# RTL8201CL.net
KiCad netlist of a schematic drawn in Altium Designer
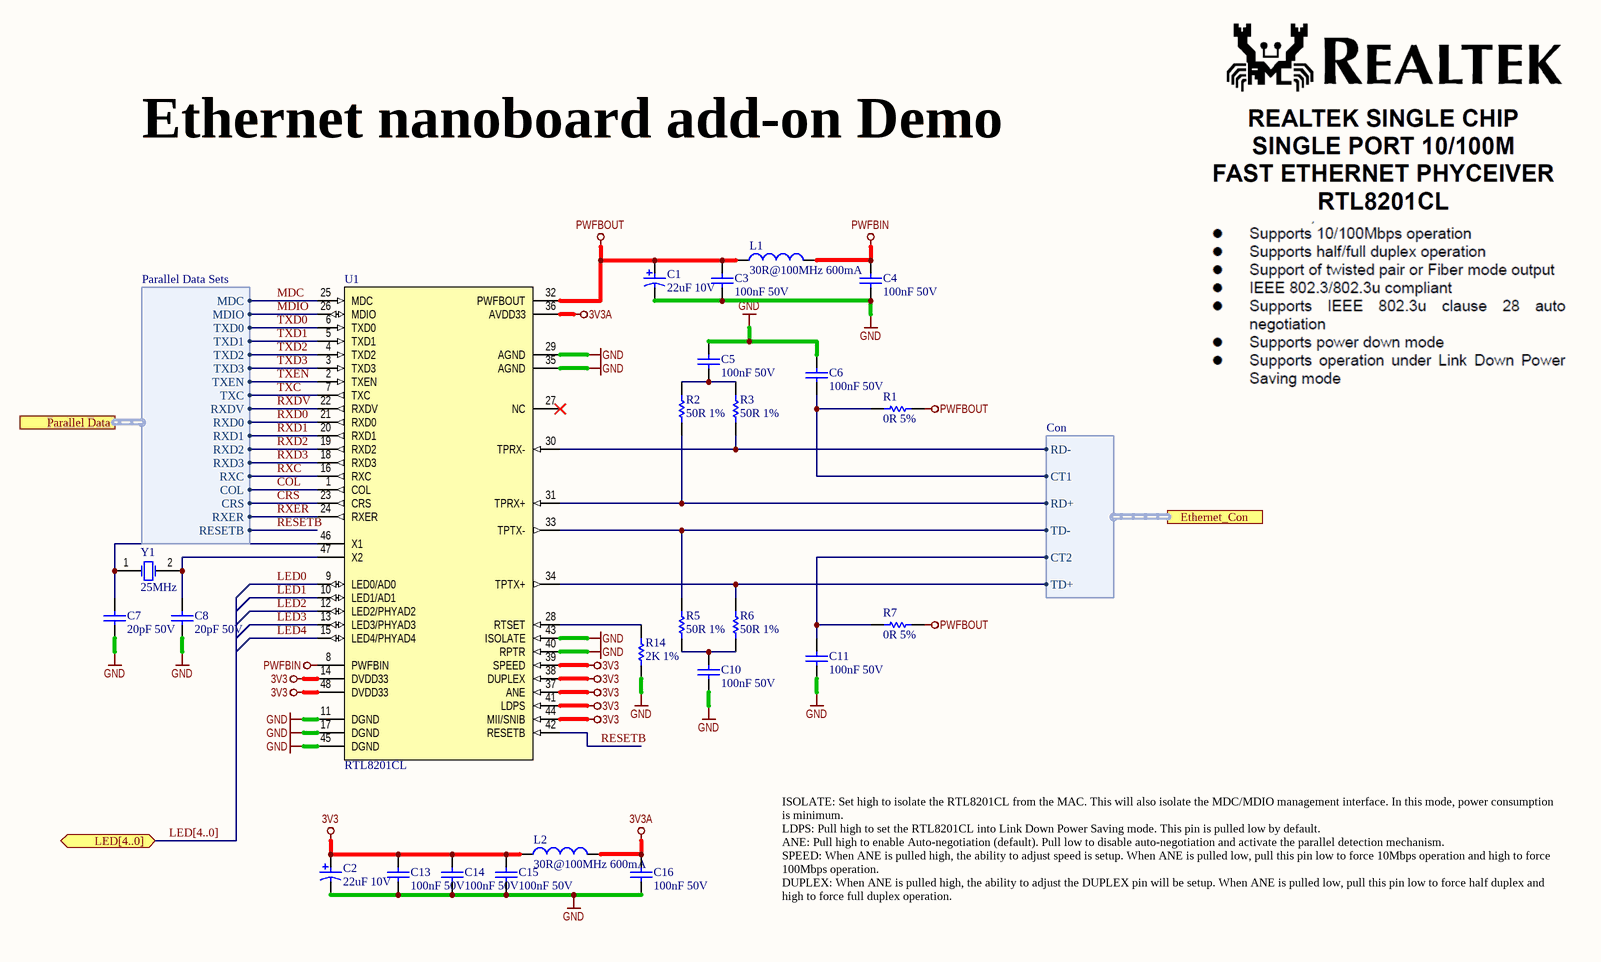
[diagram p0: RTL8201CL.SchDoc]

(export (version "E")
  (design (tool "Eeschema 10.0.6"))
  (components
    (comp (ref "C1")
      (value "22uF 10V")
      (footprint "CAPC3528")
      (description "Polar Capacitor")
      (libsource (lib "PHY") (part "CAP-P"))
    )
    (comp (ref "C2")
      (value "22uF 10V")
      (footprint "CAPC3528")
      (description "Polar Capacitor")
      (libsource (lib "PHY") (part "CAP-P"))
    )
    (comp (ref "C3")
      (value "100nF 50V")
      (footprint "CAPC2012")
      (description "Capacitor")
      (libsource (lib "PHY") (part "CAP-NP"))
    )
    (comp (ref "C4")
      (value "100nF 50V")
      (footprint "CAPC2012")
      (description "Capacitor")
      (libsource (lib "PHY") (part "CAP-NP"))
    )
    (comp (ref "C5")
      (value "100nF 50V")
      (footprint "CAPC2012")
      (description "Capacitor")
      (libsource (lib "PHY") (part "CAP-NP"))
    )
    (comp (ref "C6")
      (value "100nF 50V")
      (footprint "CAPC2012")
      (description "Capacitor")
      (libsource (lib "PHY") (part "CAP-NP"))
    )
    (comp (ref "C7")
      (value "20pF 50V")
      (footprint "CAPC2012")
      (description "Capacitor")
      (libsource (lib "PHY") (part "CAP-NP"))
    )
    (comp (ref "C8")
      (value "20pF 50V")
      (footprint "CAPC2012")
      (description "Capacitor")
      (libsource (lib "PHY") (part "CAP-NP"))
    )
    (comp (ref "C10")
      (value "100nF 50V")
      (footprint "CAPC2012")
      (description "Capacitor")
      (libsource (lib "PHY") (part "CAP-NP"))
    )
    (comp (ref "C11")
      (value "100nF 50V")
      (footprint "CAPC2012")
      (description "Capacitor")
      (libsource (lib "PHY") (part "CAP-NP"))
    )
    (comp (ref "C13")
      (value "100nF 50V")
      (footprint "CAPC2012")
      (description "Capacitor")
      (libsource (lib "PHY") (part "CAP-NP"))
    )
    (comp (ref "C14")
      (value "100nF 50V")
      (footprint "CAPC2012")
      (description "Capacitor")
      (libsource (lib "PHY") (part "CAP-NP"))
    )
    (comp (ref "C15")
      (value "100nF 50V")
      (footprint "CAPC2012")
      (description "Capacitor")
      (libsource (lib "PHY") (part "CAP-NP"))
    )
    (comp (ref "C16")
      (value "100nF 50V")
      (footprint "CAPC2012")
      (description "Capacitor")
      (libsource (lib "PHY") (part "CAP-NP"))
    )
    (comp (ref "L1")
      (value "30R@100MHz 600mA")
      (footprint "INDC2012")
      (description "Ferrite Bead")
      (libsource (lib "PHY") (part "IND-FER"))
    )
    (comp (ref "L2")
      (value "30R@100MHz 600mA")
      (footprint "INDC2012")
      (description "Ferrite Bead")
      (libsource (lib "PHY") (part "IND-FER"))
    )
    (comp (ref "R1")
      (value "0R 5%")
      (footprint "RESC2012")
      (description "Resistor")
      (libsource (lib "PHY") (part "RES"))
    )
    (comp (ref "R2")
      (value "50R 1%")
      (footprint "RESC2012")
      (description "Resistor")
      (libsource (lib "PHY") (part "RES"))
    )
    (comp (ref "R3")
      (value "50R 1%")
      (footprint "RESC2012")
      (description "Resistor")
      (libsource (lib "PHY") (part "RES"))
    )
    (comp (ref "R5")
      (value "50R 1%")
      (footprint "RESC2012")
      (description "Resistor")
      (libsource (lib "PHY") (part "RES"))
    )
    (comp (ref "R6")
      (value "50R 1%")
      (footprint "RESC2012")
      (description "Resistor")
      (libsource (lib "PHY") (part "RES"))
    )
    (comp (ref "R7")
      (value "0R 5%")
      (footprint "RESC2012")
      (description "Resistor")
      (libsource (lib "PHY") (part "RES"))
    )
    (comp (ref "R14")
      (value "2K 1%")
      (footprint "RESC2012")
      (description "Resistor")
      (libsource (lib "PHY") (part "RES"))
    )
    (comp (ref "U1")
      (value "RTL8201CL")
      (footprint "TSQFP50P900X900-48")
      (description "Realtek Ethernet PHY tranceiver")
      (libsource (lib "PHY") (part "RTL8201CL"))
    )
    (comp (ref "Y1")
      (value "25MHz")
      (footprint "XTAL_HC49SMD 20Mhz  +/-30ppm 20pf")
      (description "Surface Mount Crystal")
      (libsource (lib "PHY") (part "CRYS"))
    )
  )
  (nets
    (net (code "5") (name "/COL") (class "Default")
      (node (ref "U1") (pin "1") (pinfunction "COL_1") (pintype "output"))
    )
    (net (code "6") (name "/CRS") (class "Default")
      (node (ref "U1") (pin "23") (pinfunction "CRS_23") (pintype "output"))
    )
    (net (code "7") (name "/LED0") (class "Default")
      (node (ref "U1") (pin "9") (pinfunction "LED0/AD0_9") (pintype "bidirectional"))
    )
    (net (code "8") (name "/LED1") (class "Default")
      (node (ref "U1") (pin "10") (pinfunction "LED1/AD1_10") (pintype "bidirectional"))
    )
    (net (code "9") (name "/LED2") (class "Default")
      (node (ref "U1") (pin "12") (pinfunction "LED2/PHYAD2_12") (pintype "bidirectional"))
    )
    (net (code "10") (name "/LED3") (class "Default")
      (node (ref "U1") (pin "13") (pinfunction "LED3/PHYAD3_13") (pintype "bidirectional"))
    )
    (net (code "11") (name "/LED4") (class "Default")
      (node (ref "U1") (pin "15") (pinfunction "LED4/PHYAD4_15") (pintype "bidirectional"))
    )
    (net (code "13") (name "/MDC") (class "Default")
      (node (ref "U1") (pin "25") (pinfunction "MDC_25") (pintype "input"))
    )
    (net (code "14") (name "/MDIO") (class "Default")
      (node (ref "U1") (pin "26") (pinfunction "MDIO_26") (pintype "bidirectional"))
    )
    (net (code "15") (name "/RESETB") (class "Default")
      (node (ref "U1") (pin "42") (pinfunction "RESETB_42") (pintype "input"))
    )
    (net (code "16") (name "/RXC") (class "Default")
      (node (ref "U1") (pin "16") (pinfunction "RXC_16") (pintype "output"))
    )
    (net (code "17") (name "/RXD0") (class "Default")
      (node (ref "U1") (pin "21") (pinfunction "RXD0_21") (pintype "output"))
    )
    (net (code "18") (name "/RXD1") (class "Default")
      (node (ref "U1") (pin "20") (pinfunction "RXD1_20") (pintype "output"))
    )
    (net (code "19") (name "/RXD2") (class "Default")
      (node (ref "U1") (pin "19") (pinfunction "RXD2_19") (pintype "output"))
    )
    (net (code "20") (name "/RXD3") (class "Default")
      (node (ref "U1") (pin "18") (pinfunction "RXD3_18") (pintype "output"))
    )
    (net (code "21") (name "/RXDV") (class "Default")
      (node (ref "U1") (pin "22") (pinfunction "RXDV_22") (pintype "output"))
    )
    (net (code "22") (name "/RXER") (class "Default")
      (node (ref "U1") (pin "24") (pinfunction "RXER_24") (pintype "output"))
    )
    (net (code "23") (name "/TXC") (class "Default")
      (node (ref "U1") (pin "7") (pinfunction "TXC_7") (pintype "output"))
    )
    (net (code "24") (name "/TXD0") (class "Default")
      (node (ref "U1") (pin "6") (pinfunction "TXD0_6") (pintype "input"))
    )
    (net (code "25") (name "/TXD1") (class "Default")
      (node (ref "U1") (pin "5") (pinfunction "TXD1_5") (pintype "input"))
    )
    (net (code "26") (name "/TXD2") (class "Default")
      (node (ref "U1") (pin "4") (pinfunction "TXD2_4") (pintype "input"))
    )
    (net (code "27") (name "/TXD3") (class "Default")
      (node (ref "U1") (pin "3") (pinfunction "TXD3_3") (pintype "input"))
    )
    (net (code "28") (name "/TXEN") (class "Default")
      (node (ref "U1") (pin "2") (pinfunction "TXEN_2") (pintype "input"))
    )
    (net (code "31") (name "3V3") (class "Default")
      (node (ref "C13") (pin "2") (pinfunction "2_2") (pintype "passive"))
      (node (ref "C14") (pin "2") (pinfunction "2_2") (pintype "passive"))
      (node (ref "C15") (pin "2") (pinfunction "2_2") (pintype "passive"))
      (node (ref "C2") (pin "1") (pinfunction "1_1") (pintype "passive"))
      (node (ref "L2") (pin "1") (pinfunction "1_1") (pintype "passive"))
      (node (ref "U1") (pin "14") (pinfunction "DVDD33_14") (pintype "power_in"))
      (node (ref "U1") (pin "37") (pinfunction "ANE_37") (pintype "input"))
      (node (ref "U1") (pin "38") (pinfunction "DUPLEX_38") (pintype "input"))
      (node (ref "U1") (pin "39") (pinfunction "SPEED_39") (pintype "input"))
      (node (ref "U1") (pin "41") (pinfunction "LDPS_41") (pintype "input"))
      (node (ref "U1") (pin "44") (pinfunction "MII/SNIB_44") (pintype "input"))
      (node (ref "U1") (pin "48") (pinfunction "DVDD33_48") (pintype "power_in"))
    )
    (net (code "32") (name "3V3A") (class "Default")
      (node (ref "C16") (pin "2") (pinfunction "2_2") (pintype "passive"))
      (node (ref "L2") (pin "2") (pinfunction "2_2") (pintype "passive"))
      (node (ref "U1") (pin "36") (pinfunction "AVDD33_36") (pintype "power_in"))
    )
    (net (code "33") (name "GND") (class "Default")
      (node (ref "C1") (pin "2") (pinfunction "2_2") (pintype "passive"))
      (node (ref "C10") (pin "1") (pinfunction "1_1") (pintype "passive"))
      (node (ref "C11") (pin "1") (pinfunction "1_1") (pintype "passive"))
      (node (ref "C13") (pin "1") (pinfunction "1_1") (pintype "passive"))
      (node (ref "C14") (pin "1") (pinfunction "1_1") (pintype "passive"))
      (node (ref "C15") (pin "1") (pinfunction "1_1") (pintype "passive"))
      (node (ref "C16") (pin "1") (pinfunction "1_1") (pintype "passive"))
      (node (ref "C2") (pin "2") (pinfunction "2_2") (pintype "passive"))
      (node (ref "C3") (pin "1") (pinfunction "1_1") (pintype "passive"))
      (node (ref "C4") (pin "1") (pinfunction "1_1") (pintype "passive"))
      (node (ref "C5") (pin "2") (pinfunction "2_2") (pintype "passive"))
      (node (ref "C6") (pin "1") (pinfunction "1_1") (pintype "passive"))
      (node (ref "C7") (pin "1") (pinfunction "1_1") (pintype "passive"))
      (node (ref "C8") (pin "1") (pinfunction "1_1") (pintype "passive"))
      (node (ref "R14") (pin "1") (pinfunction "1_1") (pintype "passive"))
      (node (ref "U1") (pin "11") (pinfunction "DGND_11") (pintype "power_in"))
      (node (ref "U1") (pin "17") (pinfunction "DGND_17") (pintype "power_in"))
      (node (ref "U1") (pin "29") (pinfunction "AGND_29") (pintype "power_in"))
      (node (ref "U1") (pin "35") (pinfunction "AGND_35") (pintype "power_in"))
      (node (ref "U1") (pin "40") (pinfunction "RPTR_40") (pintype "input"))
      (node (ref "U1") (pin "43") (pinfunction "ISOLATE_43") (pintype "input"))
      (node (ref "U1") (pin "45") (pinfunction "DGND_45") (pintype "power_in"))
    )
    (net (code "34") (name "Net-(C5-Pad1)") (class "Default")
      (node (ref "C5") (pin "1") (pinfunction "1_1") (pintype "passive"))
      (node (ref "R2") (pin "2") (pinfunction "2_2") (pintype "passive"))
      (node (ref "R3") (pin "2") (pinfunction "2_2") (pintype "passive"))
    )
    (net (code "35") (name "Net-(C6-Pad2)") (class "Default")
      (node (ref "C6") (pin "2") (pinfunction "2_2") (pintype "passive"))
      (node (ref "R1") (pin "1") (pinfunction "1_1") (pintype "passive"))
    )
    (net (code "36") (name "Net-(C10-Pad2)") (class "Default")
      (node (ref "C10") (pin "2") (pinfunction "2_2") (pintype "passive"))
      (node (ref "R5") (pin "1") (pinfunction "1_1") (pintype "passive"))
      (node (ref "R6") (pin "1") (pinfunction "1_1") (pintype "passive"))
    )
    (net (code "37") (name "Net-(C11-Pad2)") (class "Default")
      (node (ref "C11") (pin "2") (pinfunction "2_2") (pintype "passive"))
      (node (ref "R7") (pin "1") (pinfunction "1_1") (pintype "passive"))
    )
    (net (code "38") (name "Net-(U1-RTSET)") (class "Default")
      (node (ref "R14") (pin "2") (pinfunction "2_2") (pintype "passive"))
      (node (ref "U1") (pin "28") (pinfunction "RTSET_28") (pintype "input"))
    )
    (net (code "39") (name "Net-(U1-TPRX+)") (class "Default")
      (node (ref "R2") (pin "1") (pinfunction "1_1") (pintype "passive"))
      (node (ref "U1") (pin "31") (pinfunction "TPRX+_31") (pintype "input"))
    )
    (net (code "40") (name "Net-(U1-TPRX-)") (class "Default")
      (node (ref "R3") (pin "1") (pinfunction "1_1") (pintype "passive"))
      (node (ref "U1") (pin "30") (pinfunction "TPRX-_30") (pintype "input"))
    )
    (net (code "41") (name "Net-(U1-TPTX+)") (class "Default")
      (node (ref "R6") (pin "2") (pinfunction "2_2") (pintype "passive"))
      (node (ref "U1") (pin "34") (pinfunction "TPTX+_34") (pintype "output"))
    )
    (net (code "42") (name "Net-(U1-TPTX-)") (class "Default")
      (node (ref "R5") (pin "2") (pinfunction "2_2") (pintype "passive"))
      (node (ref "U1") (pin "33") (pinfunction "TPTX-_33") (pintype "output"))
    )
    (net (code "43") (name "Net-(U1-X1)") (class "Default")
      (node (ref "C7") (pin "2") (pinfunction "2_2") (pintype "passive"))
      (node (ref "U1") (pin "46") (pinfunction "X1_46") (pintype "passive"))
      (node (ref "Y1") (pin "1") (pinfunction "OSC1_1") (pintype "passive"))
    )
    (net (code "44") (name "Net-(U1-X2)") (class "Default")
      (node (ref "C8") (pin "2") (pinfunction "2_2") (pintype "passive"))
      (node (ref "U1") (pin "47") (pinfunction "X2_47") (pintype "passive"))
      (node (ref "Y1") (pin "2") (pinfunction "OSC2_2") (pintype "passive"))
    )
    (net (code "45") (name "PWFBIN") (class "Default")
      (node (ref "C4") (pin "2") (pinfunction "2_2") (pintype "passive"))
      (node (ref "L1") (pin "2") (pinfunction "2_2") (pintype "passive"))
      (node (ref "U1") (pin "8") (pinfunction "PWFBIN_8") (pintype "power_in"))
    )
    (net (code "46") (name "PWFBOUT") (class "Default")
      (node (ref "C1") (pin "1") (pinfunction "1_1") (pintype "passive"))
      (node (ref "C3") (pin "2") (pinfunction "2_2") (pintype "passive"))
      (node (ref "L1") (pin "1") (pinfunction "1_1") (pintype "passive"))
      (node (ref "R1") (pin "2") (pinfunction "2_2") (pintype "passive"))
      (node (ref "R7") (pin "2") (pinfunction "2_2") (pintype "passive"))
      (node (ref "U1") (pin "32") (pinfunction "PWFBOUT_32") (pintype "power_in"))
    )
    (net (code "47") (name "unconnected-(U1-NC-Pad27)") (class "Default")
      (node (ref "U1") (pin "27") (pinfunction "NC_27") (pintype "passive+no_connect"))
    )
  )
)
